# 02-ESP32.net
KiCad netlist of a schematic drawn in Altium Designer
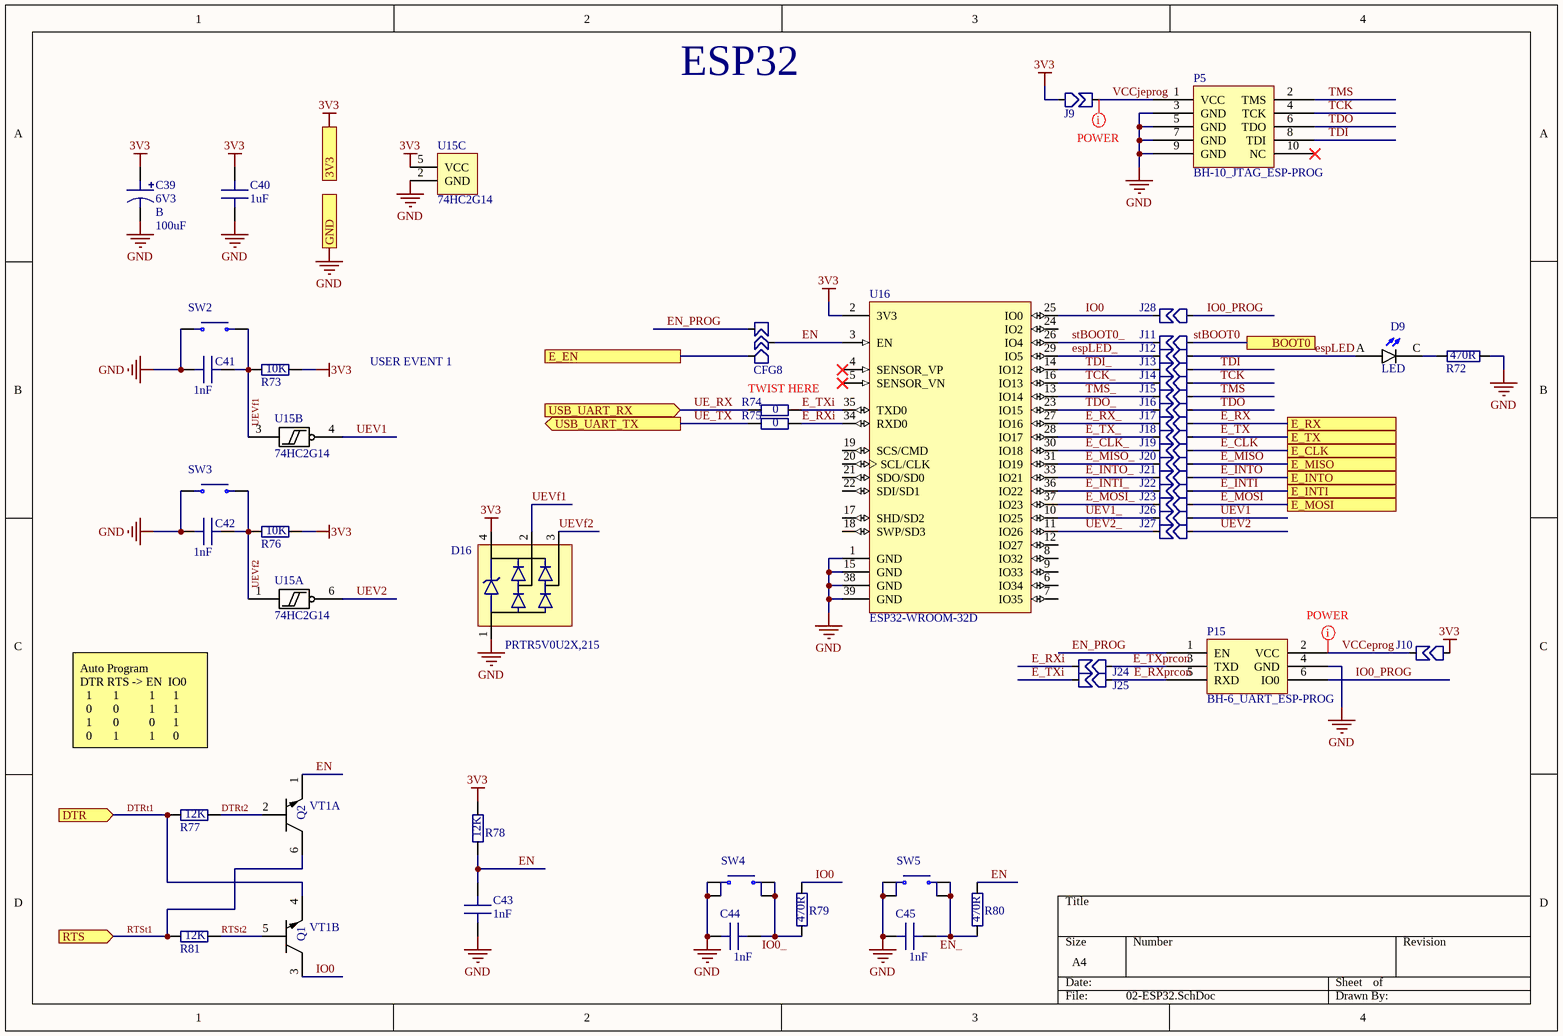
[diagram p0: 02-ESP32.SchDoc]

(export (version "E")
  (design (tool "Eeschema 10.0.6"))
  (components
    (comp (ref "C39")
      (value "100uF")
      (footprint "CAP_SIZE_B")
      (description "Tantalum capacitor")
      (fields (field (name "VOLTAGE") "6V3") (field (name "SIZE") "B"))
      (libsource (lib "A.Shelestov_Capacitors") (part "CAP_B_100uF_6V3"))
    )
    (comp (ref "C40")
      (value "1uF")
      (footprint "C0805")
      (description "Ceramic capacitor")
      (fields (field (name "VOLTAGE") "25V"))
      (libsource (lib "A.Shelestov_Capacitors") (part "C0805_1uF_25V"))
    )
    (comp (ref "C41")
      (value "1nF")
      (footprint "C0603")
      (description "Ceramic capacitor")
      (fields (field (name "VOLTAGE") "25V"))
      (libsource (lib "A.Shelestov_Capacitors") (part "C0603_1nF_25V"))
    )
    (comp (ref "C42")
      (value "1nF")
      (footprint "C0603")
      (description "Ceramic capacitor")
      (fields (field (name "VOLTAGE") "25V"))
      (libsource (lib "A.Shelestov_Capacitors") (part "C0603_1nF_25V"))
    )
    (comp (ref "C43")
      (value "1nF")
      (footprint "C0603")
      (description "Ceramic capacitor")
      (fields (field (name "VOLTAGE") "25V"))
      (libsource (lib "A.Shelestov_Capacitors") (part "C0603_1nF_25V"))
    )
    (comp (ref "C44")
      (value "1nF")
      (footprint "C0603")
      (description "Ceramic capacitor")
      (fields (field (name "VOLTAGE") "25V"))
      (libsource (lib "A.Shelestov_Capacitors") (part "C0603_1nF_25V"))
    )
    (comp (ref "C45")
      (value "1nF")
      (footprint "C0603")
      (description "Ceramic capacitor")
      (fields (field (name "VOLTAGE") "25V"))
      (libsource (lib "A.Shelestov_Capacitors") (part "C0603_1nF_25V"))
    )
    (comp (ref "CFG8")
      (value "CFG3_ORTH")
      (footprint "CFG_0603")
      (libsource (lib "ComponentsLib") (part "CFG3_ORTH"))
    )
    (comp (ref "D9")
      (value "LED")
      (footprint "LED_0604")
      (description "Led General")
      (fields (field (name "MF") "Dialight") (field (name "MP") "598-8140-107F"))
      (libsource (lib "ComponentsLib") (part "LED"))
    )
    (comp (ref "D16")
      (value "PRTR5V0U2X,215")
      (footprint "SOT143B")
      (description "PRTR5V0U2X - Ultra low capacitance double rail-to-rail ESD protection diode")
      (fields (field (name "MF") "Nexperia USA"))
      (libsource (lib "ComponentsLib") (part "PRTR5V0U2X,215"))
    )
    (comp (ref "J9") (value "CFG2") (footprint "CFG_J_0603") (libsource (lib "ComponentsLib") (part "CFG2")))
    (comp (ref "J10") (value "CFG2") (footprint "CFG_J_0603") (libsource (lib "ComponentsLib") (part "CFG2")))
    (comp (ref "J11") (value "CFG2") (footprint "CFG_J_0603") (libsource (lib "ComponentsLib") (part "CFG2")))
    (comp (ref "J12") (value "CFG2") (footprint "CFG_J_0603") (libsource (lib "ComponentsLib") (part "CFG2")))
    (comp (ref "J13") (value "CFG2") (footprint "CFG_J_0603") (libsource (lib "ComponentsLib") (part "CFG2")))
    (comp (ref "J14") (value "CFG2") (footprint "CFG_J_0603") (libsource (lib "ComponentsLib") (part "CFG2")))
    (comp (ref "J15") (value "CFG2") (footprint "CFG_J_0603") (libsource (lib "ComponentsLib") (part "CFG2")))
    (comp (ref "J16") (value "CFG2") (footprint "CFG_J_0603") (libsource (lib "ComponentsLib") (part "CFG2")))
    (comp (ref "J17") (value "CFG2") (footprint "CFG_J_0603") (libsource (lib "ComponentsLib") (part "CFG2")))
    (comp (ref "J18") (value "CFG2") (footprint "CFG_J_0603") (libsource (lib "ComponentsLib") (part "CFG2")))
    (comp (ref "J19") (value "CFG2") (footprint "CFG_J_0603") (libsource (lib "ComponentsLib") (part "CFG2")))
    (comp (ref "J20") (value "CFG2") (footprint "CFG_J_0603") (libsource (lib "ComponentsLib") (part "CFG2")))
    (comp (ref "J21") (value "CFG2") (footprint "CFG_J_0603") (libsource (lib "ComponentsLib") (part "CFG2")))
    (comp (ref "J22") (value "CFG2") (footprint "CFG_J_0603") (libsource (lib "ComponentsLib") (part "CFG2")))
    (comp (ref "J23") (value "CFG2") (footprint "CFG_J_0603") (libsource (lib "ComponentsLib") (part "CFG2")))
    (comp (ref "J24") (value "CFG2") (footprint "CFG_J_0603") (libsource (lib "ComponentsLib") (part "CFG2")))
    (comp (ref "J25") (value "CFG2") (footprint "CFG_J_0603") (libsource (lib "ComponentsLib") (part "CFG2")))
    (comp (ref "J26") (value "CFG2") (footprint "CFG_J_0603") (libsource (lib "ComponentsLib") (part "CFG2")))
    (comp (ref "J27") (value "CFG2") (footprint "CFG_J_0603") (libsource (lib "ComponentsLib") (part "CFG2")))
    (comp (ref "J28") (value "CFG2") (footprint "CFG_J_0603") (libsource (lib "ComponentsLib") (part "CFG2")))
    (comp (ref "P5")
      (value "BH-10_JTAG_ESP-PROG")
      (footprint "BH-10-SMD-1.27")
      (description "1,27 mm 2x5 Header")
      (libsource (lib "ComponentsLib") (part "BH-10_JTAG_ESP-PROG"))
    )
    (comp (ref "P15")
      (value "BH-6_UART_ESP-PROG")
      (footprint "BH-6-SMD-1.27")
      (description "1,27 mm 2x3 Header")
      (libsource (lib "ComponentsLib") (part "BH-6_UART_ESP-PROG"))
    )
    (comp (ref "R72")
      (value "~")
      (footprint "R0603")
      (description "Resistor General")
      (fields (field (name "TOLERANCE") "5%") (field (name "RESISTANCE") "470R"))
      (libsource (lib "A.Shelestov_Resistors") (part "R0603_470R"))
    )
    (comp (ref "R73")
      (value "~")
      (footprint "R0603")
      (description "Resistor General")
      (fields (field (name "TOLERANCE") "5%") (field (name "RESISTANCE") "10K"))
      (libsource (lib "A.Shelestov_Resistors") (part "R0603_10K"))
    )
    (comp (ref "R74")
      (value "~")
      (footprint "R0402")
      (description "Resistor General")
      (fields (field (name "RESISTANCE") "0"))
      (libsource (lib "A.Shelestov_Resistors") (part "R0402_0R"))
    )
    (comp (ref "R75")
      (value "~")
      (footprint "R0402")
      (description "Resistor General")
      (fields (field (name "RESISTANCE") "0"))
      (libsource (lib "A.Shelestov_Resistors") (part "R0402_0R"))
    )
    (comp (ref "R76")
      (value "~")
      (footprint "R0603")
      (description "Resistor General")
      (fields (field (name "TOLERANCE") "5%") (field (name "RESISTANCE") "10K"))
      (libsource (lib "A.Shelestov_Resistors") (part "R0603_10K"))
    )
    (comp (ref "R77")
      (value "~")
      (footprint "R0603")
      (description "Resistor General")
      (fields (field (name "TOLERANCE") "5%") (field (name "RESISTANCE") "12K"))
      (libsource (lib "A.Shelestov_Resistors") (part "R0603_12K"))
    )
    (comp (ref "R78")
      (value "~")
      (footprint "R0603")
      (description "Resistor General")
      (fields (field (name "TOLERANCE") "5%") (field (name "RESISTANCE") "12K"))
      (libsource (lib "A.Shelestov_Resistors") (part "R0603_12K"))
    )
    (comp (ref "R79")
      (value "~")
      (footprint "R0603")
      (description "Resistor General")
      (fields (field (name "TOLERANCE") "5%") (field (name "RESISTANCE") "470R"))
      (libsource (lib "A.Shelestov_Resistors") (part "R0603_470R"))
    )
    (comp (ref "R80")
      (value "~")
      (footprint "R0603")
      (description "Resistor General")
      (fields (field (name "TOLERANCE") "5%") (field (name "RESISTANCE") "470R"))
      (libsource (lib "A.Shelestov_Resistors") (part "R0603_470R"))
    )
    (comp (ref "R81")
      (value "~")
      (footprint "R0603")
      (description "Resistor General")
      (fields (field (name "TOLERANCE") "5%") (field (name "RESISTANCE") "12K"))
      (libsource (lib "A.Shelestov_Resistors") (part "R0603_12K"))
    )
    (comp (ref "SW2")
      (value "SWITCH_GEN_2P")
      (footprint "SW_TACTM-35N-F")
      (description "SWITCH DIP 4.3 mm")
      (libsource (lib "ComponentsLib") (part "SWITCH_GEN_2P"))
    )
    (comp (ref "SW3")
      (value "SWITCH_GEN_2P")
      (footprint "SW_TACTM-35N-F")
      (description "SWITCH DIP 4.3 mm")
      (libsource (lib "ComponentsLib") (part "SWITCH_GEN_2P"))
    )
    (comp (ref "SW4")
      (value "SWITCH_GEN_4P")
      (footprint "SW_4x4x1.5")
      (description "SWITCH DIP 4.3 mm")
      (libsource (lib "ComponentsLib") (part "SWITCH_GEN_4P"))
    )
    (comp (ref "SW5")
      (value "SWITCH_GEN_4P")
      (footprint "SW_4x4x1.5")
      (description "SWITCH DIP 4.3 mm")
      (libsource (lib "ComponentsLib") (part "SWITCH_GEN_4P"))
    )
    (comp (ref "U15")
      (value "74HC2G14")
      (footprint "SOT363/SOT65P210X110-6N")
      (description "Dual inverting Schmitt trigger")
      (libsource (lib "ComponentsLib") (part "74HC2G14"))
    )
    (comp (ref "U16")
      (value "ESP32-WROOM-32D")
      (footprint "ESP32-WROOM-32")
      (description "IC: SoC; GPIO, I2C, I2S, IR, SD, SDIO, SPI, UART; 2.7Г·3.6VDC; 20dBm")
      (fields (field (name "MF") "Espressif Systems"))
      (libsource (lib "ComponentsLib") (part "ESP32-WROOM-32D"))
    )
    (comp (ref "VT1")
      (value "BC847BDW1T1G")
      (footprint "SOT363/SOT65P210X110-6N")
      (description "Dual General Purpose Transistors NPN SOT 363")
      (libsource (lib "ComponentsLib") (part "BC847BDW1T1G"))
    )
  )
  (nets
    (net (code "1") (name "/DTRt1") (class "Default")
      (node (ref "R77") (pin "1") (pinfunction "1_1") (pintype "passive"))
      (node (ref "VT1") (pin "4") (pinfunction "4_4") (pintype "passive"))
    )
    (net (code "2") (name "/DTRt2") (class "Default")
      (node (ref "R77") (pin "2") (pinfunction "2_2") (pintype "passive"))
      (node (ref "VT1") (pin "2") (pinfunction "2_2") (pintype "passive"))
    )
    (net (code "3") (name "/EN") (class "Default")
      (node (ref "C43") (pin "2") (pinfunction "2_2") (pintype "passive"))
      (node (ref "CFG8") (pin "2") (pinfunction "IN_2") (pintype "passive"))
      (node (ref "R78") (pin "1") (pinfunction "1_1") (pintype "passive"))
      (node (ref "R80") (pin "2") (pinfunction "2_2") (pintype "passive"))
      (node (ref "U16") (pin "3") (pinfunction "EN_3") (pintype "input"))
      (node (ref "VT1") (pin "1") (pinfunction "1_1") (pintype "passive"))
    )
    (net (code "4") (name "/EN_") (class "Default")
      (node (ref "C45") (pin "2") (pinfunction "2_2") (pintype "passive"))
      (node (ref "R80") (pin "1") (pinfunction "1_1") (pintype "passive"))
      (node (ref "SW5") (pin "2") (pinfunction "2_2") (pintype "passive"))
      (node (ref "SW5") (pin "4") (pinfunction "4_4") (pintype "passive"))
    )
    (net (code "5") (name "/EN_PROG") (class "Default")
      (node (ref "CFG8") (pin "1") (pinfunction "A_1") (pintype "passive"))
      (node (ref "P15") (pin "1") (pinfunction "EN_1") (pintype "passive"))
    )
    (net (code "6") (name "/E_CLK") (class "Default")
      (node (ref "J19") (pin "2") (pinfunction "IN_2") (pintype "passive"))
    )
    (net (code "7") (name "/E_CLK_") (class "Default")
      (node (ref "J19") (pin "1") (pinfunction "A_1") (pintype "passive"))
      (node (ref "U16") (pin "30") (pinfunction "IO18_30") (pintype "bidirectional"))
    )
    (net (code "8") (name "/E_EN") (class "Default")
      (node (ref "CFG8") (pin "3") (pinfunction "B_3") (pintype "passive"))
    )
    (net (code "9") (name "/E_INTI") (class "Default")
      (node (ref "J22") (pin "2") (pinfunction "IN_2") (pintype "passive"))
    )
    (net (code "10") (name "/E_INTI_") (class "Default")
      (node (ref "J22") (pin "1") (pinfunction "A_1") (pintype "passive"))
      (node (ref "U16") (pin "36") (pinfunction "IO22_36") (pintype "bidirectional"))
    )
    (net (code "11") (name "/E_INTO") (class "Default")
      (node (ref "J21") (pin "2") (pinfunction "IN_2") (pintype "passive"))
    )
    (net (code "12") (name "/E_INTO_") (class "Default")
      (node (ref "J21") (pin "1") (pinfunction "A_1") (pintype "passive"))
      (node (ref "U16") (pin "33") (pinfunction "IO21_33") (pintype "bidirectional"))
    )
    (net (code "13") (name "/E_MISO") (class "Default")
      (node (ref "J20") (pin "2") (pinfunction "IN_2") (pintype "passive"))
    )
    (net (code "14") (name "/E_MISO_") (class "Default")
      (node (ref "J20") (pin "1") (pinfunction "A_1") (pintype "passive"))
      (node (ref "U16") (pin "31") (pinfunction "IO19_31") (pintype "bidirectional"))
    )
    (net (code "15") (name "/E_MOSI") (class "Default")
      (node (ref "J23") (pin "2") (pinfunction "IN_2") (pintype "passive"))
    )
    (net (code "16") (name "/E_MOSI_") (class "Default")
      (node (ref "J23") (pin "1") (pinfunction "A_1") (pintype "passive"))
      (node (ref "U16") (pin "37") (pinfunction "IO23_37") (pintype "bidirectional"))
    )
    (net (code "17") (name "/E_RX") (class "Default")
      (node (ref "J17") (pin "2") (pinfunction "IN_2") (pintype "passive"))
    )
    (net (code "18") (name "/E_RX_") (class "Default")
      (node (ref "J17") (pin "1") (pinfunction "A_1") (pintype "passive"))
      (node (ref "U16") (pin "27") (pinfunction "IO16_27") (pintype "bidirectional"))
    )
    (net (code "19") (name "/E_RXi") (class "Default")
      (node (ref "J24") (pin "1") (pinfunction "A_1") (pintype "passive"))
      (node (ref "R75") (pin "2") (pinfunction "2_2") (pintype "passive"))
      (node (ref "U16") (pin "34") (pinfunction "RXD0_34") (pintype "bidirectional"))
    )
    (net (code "20") (name "/E_RXprcon") (class "Default")
      (node (ref "J25") (pin "2") (pinfunction "IN_2") (pintype "passive"))
      (node (ref "P15") (pin "5") (pinfunction "RXD_5") (pintype "passive"))
    )
    (net (code "21") (name "/E_TX") (class "Default")
      (node (ref "J18") (pin "2") (pinfunction "IN_2") (pintype "passive"))
    )
    (net (code "22") (name "/E_TX_") (class "Default")
      (node (ref "J18") (pin "1") (pinfunction "A_1") (pintype "passive"))
      (node (ref "U16") (pin "28") (pinfunction "IO17_28") (pintype "bidirectional"))
    )
    (net (code "23") (name "/E_TXi") (class "Default")
      (node (ref "J25") (pin "1") (pinfunction "A_1") (pintype "passive"))
      (node (ref "R74") (pin "2") (pinfunction "2_2") (pintype "passive"))
      (node (ref "U16") (pin "35") (pinfunction "TXD0_35") (pintype "bidirectional"))
    )
    (net (code "24") (name "/E_TXprcon") (class "Default")
      (node (ref "J24") (pin "2") (pinfunction "IN_2") (pintype "passive"))
      (node (ref "P15") (pin "3") (pinfunction "TXD_3") (pintype "passive"))
    )
    (net (code "25") (name "/IO0") (class "Default")
      (node (ref "J28") (pin "1") (pinfunction "A_1") (pintype "passive"))
      (node (ref "R79") (pin "2") (pinfunction "2_2") (pintype "passive"))
      (node (ref "U16") (pin "25") (pinfunction "IO0_25") (pintype "bidirectional"))
      (node (ref "VT1") (pin "3") (pinfunction "3_3") (pintype "passive"))
    )
    (net (code "26") (name "/IO0_") (class "Default")
      (node (ref "C44") (pin "2") (pinfunction "2_2") (pintype "passive"))
      (node (ref "R79") (pin "1") (pinfunction "1_1") (pintype "passive"))
      (node (ref "SW4") (pin "2") (pinfunction "2_2") (pintype "passive"))
      (node (ref "SW4") (pin "4") (pinfunction "4_4") (pintype "passive"))
    )
    (net (code "27") (name "/IO0_PROG") (class "Default")
      (node (ref "J28") (pin "2") (pinfunction "IN_2") (pintype "passive"))
      (node (ref "P15") (pin "6") (pinfunction "IO0_6") (pintype "passive"))
    )
    (net (code "28") (name "/RTSt1") (class "Default")
      (node (ref "R81") (pin "1") (pinfunction "1_1") (pintype "passive"))
      (node (ref "VT1") (pin "6") (pinfunction "6_6") (pintype "passive"))
    )
    (net (code "29") (name "/RTSt2") (class "Default")
      (node (ref "R81") (pin "2") (pinfunction "2_2") (pintype "passive"))
      (node (ref "VT1") (pin "5") (pinfunction "5_5") (pintype "passive"))
    )
    (net (code "30") (name "/TCK") (class "Default")
      (node (ref "J14") (pin "2") (pinfunction "IN_2") (pintype "passive"))
      (node (ref "P5") (pin "4") (pinfunction "TCK_4") (pintype "passive"))
    )
    (net (code "31") (name "/TCK_") (class "Default")
      (node (ref "J14") (pin "1") (pinfunction "A_1") (pintype "passive"))
      (node (ref "U16") (pin "16") (pinfunction "IO13_16") (pintype "bidirectional"))
    )
    (net (code "32") (name "/TDI") (class "Default")
      (node (ref "J13") (pin "2") (pinfunction "IN_2") (pintype "passive"))
      (node (ref "P5") (pin "8") (pinfunction "TDI_8") (pintype "passive"))
    )
    (net (code "33") (name "/TDI_") (class "Default")
      (node (ref "J13") (pin "1") (pinfunction "A_1") (pintype "passive"))
      (node (ref "U16") (pin "14") (pinfunction "IO12_14") (pintype "bidirectional"))
    )
    (net (code "34") (name "/TDO") (class "Default")
      (node (ref "J16") (pin "2") (pinfunction "IN_2") (pintype "passive"))
      (node (ref "P5") (pin "6") (pinfunction "TDO_6") (pintype "passive"))
    )
    (net (code "35") (name "/TDO_") (class "Default")
      (node (ref "J16") (pin "1") (pinfunction "A_1") (pintype "passive"))
      (node (ref "U16") (pin "23") (pinfunction "IO15_23") (pintype "bidirectional"))
    )
    (net (code "36") (name "/TMS") (class "Default")
      (node (ref "J15") (pin "2") (pinfunction "IN_2") (pintype "passive"))
      (node (ref "P5") (pin "2") (pinfunction "TMS_2") (pintype "passive"))
    )
    (net (code "37") (name "/TMS_") (class "Default")
      (node (ref "J15") (pin "1") (pinfunction "A_1") (pintype "passive"))
      (node (ref "U16") (pin "13") (pinfunction "IO14_13") (pintype "bidirectional"))
    )
    (net (code "38") (name "/UEV1") (class "Default")
      (node (ref "J26") (pin "2") (pinfunction "IN_2") (pintype "passive"))
      (node (ref "U15") (pin "4") (pinfunction "2Y_4") (pintype "passive"))
    )
    (net (code "39") (name "/UEV1_") (class "Default")
      (node (ref "J26") (pin "1") (pinfunction "A_1") (pintype "passive"))
      (node (ref "U16") (pin "10") (pinfunction "IO25_10") (pintype "bidirectional"))
    )
    (net (code "40") (name "/UEV2") (class "Default")
      (node (ref "J27") (pin "2") (pinfunction "IN_2") (pintype "passive"))
      (node (ref "U15") (pin "6") (pinfunction "1Y_6") (pintype "passive"))
    )
    (net (code "41") (name "/UEV2_") (class "Default")
      (node (ref "J27") (pin "1") (pinfunction "A_1") (pintype "passive"))
      (node (ref "U16") (pin "11") (pinfunction "IO26_11") (pintype "bidirectional"))
    )
    (net (code "42") (name "/UEVf1") (class "Default")
      (node (ref "C41") (pin "1") (pinfunction "1_1") (pintype "passive"))
      (node (ref "D16") (pin "2") (pinfunction "P$2_2") (pintype "passive"))
      (node (ref "R73") (pin "1") (pinfunction "1_1") (pintype "passive"))
      (node (ref "SW2") (pin "2") (pinfunction "2_2") (pintype "passive"))
      (node (ref "U15") (pin "3") (pinfunction "2A_3") (pintype "passive"))
    )
    (net (code "43") (name "/UEVf2") (class "Default")
      (node (ref "C42") (pin "1") (pinfunction "1_1") (pintype "passive"))
      (node (ref "D16") (pin "3") (pinfunction "P$3_3") (pintype "passive"))
      (node (ref "R76") (pin "1") (pinfunction "1_1") (pintype "passive"))
      (node (ref "SW3") (pin "2") (pinfunction "2_2") (pintype "passive"))
      (node (ref "U15") (pin "1") (pinfunction "1A_1") (pintype "passive"))
    )
    (net (code "44") (name "/UE_RX") (class "Default")
      (node (ref "R74") (pin "1") (pinfunction "1_1") (pintype "passive"))
    )
    (net (code "45") (name "/UE_TX") (class "Default")
      (node (ref "R75") (pin "1") (pinfunction "1_1") (pintype "passive"))
    )
    (net (code "46") (name "/VCCeprog") (class "Default")
      (node (ref "J10") (pin "1") (pinfunction "A_1") (pintype "passive"))
      (node (ref "P15") (pin "2") (pinfunction "VCC_2") (pintype "passive"))
    )
    (net (code "47") (name "/VCCjeprog") (class "Default")
      (node (ref "J9") (pin "1") (pinfunction "A_1") (pintype "passive"))
      (node (ref "P5") (pin "1") (pinfunction "VCC_1") (pintype "passive"))
    )
    (net (code "48") (name "/espLED") (class "Default")
      (node (ref "D9") (pin "A") (pinfunction "A_A") (pintype "passive"))
      (node (ref "J12") (pin "2") (pinfunction "IN_2") (pintype "passive"))
    )
    (net (code "49") (name "/espLED_") (class "Default")
      (node (ref "J12") (pin "1") (pinfunction "A_1") (pintype "passive"))
      (node (ref "U16") (pin "29") (pinfunction "IO5_29") (pintype "bidirectional"))
    )
    (net (code "50") (name "/stBOOT0") (class "Default")
      (node (ref "J11") (pin "2") (pinfunction "IN_2") (pintype "passive"))
    )
    (net (code "51") (name "/stBOOT0_") (class "Default")
      (node (ref "J11") (pin "1") (pinfunction "A_1") (pintype "passive"))
      (node (ref "U16") (pin "26") (pinfunction "IO4_26") (pintype "bidirectional"))
    )
    (net (code "52") (name "3V3") (class "Default")
      (node (ref "C39") (pin "1") (pinfunction "1_1") (pintype "passive"))
      (node (ref "C40") (pin "2") (pinfunction "2_2") (pintype "passive"))
      (node (ref "D16") (pin "4") (pinfunction "P$4_4") (pintype "passive"))
      (node (ref "J10") (pin "2") (pinfunction "IN_2") (pintype "passive"))
      (node (ref "J9") (pin "2") (pinfunction "IN_2") (pintype "passive"))
      (node (ref "R73") (pin "2") (pinfunction "2_2") (pintype "passive"))
      (node (ref "R76") (pin "2") (pinfunction "2_2") (pintype "passive"))
      (node (ref "R78") (pin "2") (pinfunction "2_2") (pintype "passive"))
      (node (ref "U15") (pin "5") (pinfunction "VCC_5") (pintype "passive"))
      (node (ref "U16") (pin "2") (pinfunction "3V3_2") (pintype "power_in"))
    )
    (net (code "53") (name "GND") (class "Default")
      (node (ref "C39") (pin "2") (pinfunction "2_2") (pintype "passive"))
      (node (ref "C40") (pin "1") (pinfunction "1_1") (pintype "passive"))
      (node (ref "C41") (pin "2") (pinfunction "2_2") (pintype "passive"))
      (node (ref "C42") (pin "2") (pinfunction "2_2") (pintype "passive"))
      (node (ref "C43") (pin "1") (pinfunction "1_1") (pintype "passive"))
      (node (ref "C44") (pin "1") (pinfunction "1_1") (pintype "passive"))
      (node (ref "C45") (pin "1") (pinfunction "1_1") (pintype "passive"))
      (node (ref "D16") (pin "1") (pinfunction "P$1_1") (pintype "passive"))
      (node (ref "P15") (pin "4") (pinfunction "GND_4") (pintype "passive"))
      (node (ref "P5") (pin "3") (pinfunction "GND_3") (pintype "passive"))
      (node (ref "P5") (pin "5") (pinfunction "GND_5") (pintype "passive"))
      (node (ref "P5") (pin "7") (pinfunction "GND_7") (pintype "passive"))
      (node (ref "P5") (pin "9") (pinfunction "GND_9") (pintype "passive"))
      (node (ref "R72") (pin "2") (pinfunction "2_2") (pintype "passive"))
      (node (ref "SW2") (pin "1") (pinfunction "1_1") (pintype "passive"))
      (node (ref "SW3") (pin "1") (pinfunction "1_1") (pintype "passive"))
      (node (ref "SW4") (pin "1") (pinfunction "1_1") (pintype "passive"))
      (node (ref "SW4") (pin "3") (pinfunction "3_3") (pintype "passive"))
      (node (ref "SW5") (pin "1") (pinfunction "1_1") (pintype "passive"))
      (node (ref "SW5") (pin "3") (pinfunction "3_3") (pintype "passive"))
      (node (ref "U15") (pin "2") (pinfunction "GND_2") (pintype "passive"))
      (node (ref "U16") (pin "1") (pinfunction "GND_1") (pintype "power_in"))
      (node (ref "U16") (pin "15") (pinfunction "GND_15") (pintype "power_in"))
      (node (ref "U16") (pin "38") (pinfunction "GND_38") (pintype "power_in"))
      (node (ref "U16") (pin "39") (pinfunction "GND_39") (pintype "power_in"))
    )
    (net (code "54") (name "Net-(D9-PadC)") (class "Default")
      (node (ref "D9") (pin "C") (pinfunction "C_C") (pintype "passive"))
      (node (ref "R72") (pin "1") (pinfunction "1_1") (pintype "passive"))
    )
    (net (code "55") (name "unconnected-(P5-NC-Pad10)") (class "Default")
      (node (ref "P5") (pin "10") (pinfunction "NC_10") (pintype "passive+no_connect"))
    )
    (net (code "56") (name "unconnected-(U16-IO2-Pad24)") (class "Default")
      (node (ref "U16") (pin "24") (pinfunction "IO2_24") (pintype "bidirectional"))
    )
    (net (code "57") (name "unconnected-(U16-IO27-Pad12)") (class "Default")
      (node (ref "U16") (pin "12") (pinfunction "IO27_12") (pintype "bidirectional"))
    )
    (net (code "58") (name "unconnected-(U16-IO32-Pad8)") (class "Default")
      (node (ref "U16") (pin "8") (pinfunction "IO32_8") (pintype "bidirectional"))
    )
    (net (code "59") (name "unconnected-(U16-IO33-Pad9)") (class "Default")
      (node (ref "U16") (pin "9") (pinfunction "IO33_9") (pintype "bidirectional"))
    )
    (net (code "60") (name "unconnected-(U16-IO34-Pad6)") (class "Default")
      (node (ref "U16") (pin "6") (pinfunction "IO34_6") (pintype "bidirectional"))
    )
    (net (code "61") (name "unconnected-(U16-IO35-Pad7)") (class "Default")
      (node (ref "U16") (pin "7") (pinfunction "IO35_7") (pintype "bidirectional"))
    )
    (net (code "62") (name "unconnected-(U16-SCL{slash}CLK-Pad20)") (class "Default")
      (node (ref "U16") (pin "20") (pinfunction "SCL/CLK_20") (pintype "bidirectional"))
    )
    (net (code "63") (name "unconnected-(U16-SCS{slash}CMD-Pad19)") (class "Default")
      (node (ref "U16") (pin "19") (pinfunction "SCS/CMD_19") (pintype "bidirectional"))
    )
    (net (code "64") (name "unconnected-(U16-SDI{slash}SD1-Pad22)") (class "Default")
      (node (ref "U16") (pin "22") (pinfunction "SDI/SD1_22") (pintype "bidirectional"))
    )
    (net (code "65") (name "unconnected-(U16-SDO{slash}SD0-Pad21)") (class "Default")
      (node (ref "U16") (pin "21") (pinfunction "SDO/SD0_21") (pintype "bidirectional"))
    )
    (net (code "66") (name "unconnected-(U16-SENSOR_VN-Pad5)") (class "Default")
      (node (ref "U16") (pin "5") (pinfunction "SENSOR_VN_5") (pintype "input+no_connect"))
    )
    (net (code "67") (name "unconnected-(U16-SENSOR_VP-Pad4)") (class "Default")
      (node (ref "U16") (pin "4") (pinfunction "SENSOR_VP_4") (pintype "input+no_connect"))
    )
    (net (code "68") (name "unconnected-(U16-SHD{slash}SD2-Pad17)") (class "Default")
      (node (ref "U16") (pin "17") (pinfunction "SHD/SD2_17") (pintype "bidirectional"))
    )
    (net (code "69") (name "unconnected-(U16-SWP{slash}SD3-Pad18)") (class "Default")
      (node (ref "U16") (pin "18") (pinfunction "SWP/SD3_18") (pintype "bidirectional"))
    )
  )
)
